# Pulse_Generator.net
KiCad netlist of a schematic drawn in EAGLE
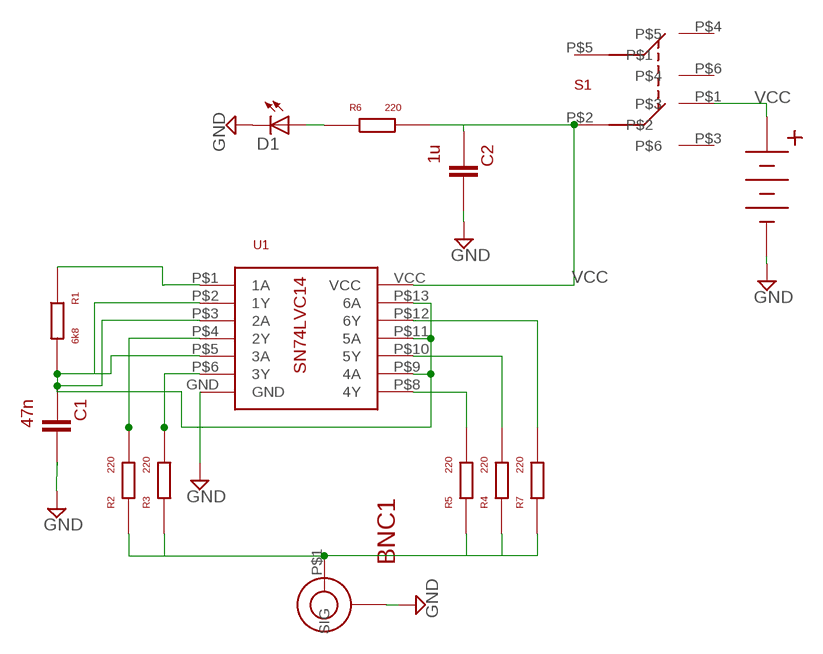
[diagram p0: schematic, sheet 1]

(export (version "E")
  (design (tool "Eeschema 10.0.6"))
  (components
    (comp (ref "BNC1")
      (value "TE-1-337543")
      (footprint "eagle-import:PCBBNC")
      (libsource (lib "eagle-import") (part "TE-1-337543"))
    )
    (comp (ref "C1")
      (value "47n")
      (footprint "eagle-import:1206CAP")
      (libsource (lib "eagle-import") (part "1206LED"))
    )
    (comp (ref "C2")
      (value "1u")
      (footprint "eagle-import:1206CAP")
      (libsource (lib "eagle-import") (part "1206LED"))
    )
    (comp (ref "D1")
      (value "1206LEDDIODE")
      (footprint "eagle-import:1206")
      (libsource (lib "eagle-import") (part "1206LEDDIODE"))
    )
    (comp (ref "R1")
      (value "6k8")
      (footprint "eagle-import:1206")
      (libsource (lib "eagle-import") (part "1206RESISTOR"))
    )
    (comp (ref "R2")
      (value "220")
      (footprint "eagle-import:1206")
      (libsource (lib "eagle-import") (part "1206RESISTOR"))
    )
    (comp (ref "R3")
      (value "220")
      (footprint "eagle-import:1206")
      (libsource (lib "eagle-import") (part "1206RESISTOR"))
    )
    (comp (ref "R4")
      (value "220")
      (footprint "eagle-import:1206")
      (libsource (lib "eagle-import") (part "1206RESISTOR"))
    )
    (comp (ref "R5")
      (value "220")
      (footprint "eagle-import:1206")
      (libsource (lib "eagle-import") (part "1206RESISTOR"))
    )
    (comp (ref "R6")
      (value "220")
      (footprint "eagle-import:1206")
      (libsource (lib "eagle-import") (part "1206RESISTOR"))
    )
    (comp (ref "R7")
      (value "220")
      (footprint "eagle-import:1206")
      (libsource (lib "eagle-import") (part "1206RESISTOR"))
    )
    (comp (ref "S1")
      (value "JS202011SCQN")
      (footprint "eagle-import:JS202011SCQN")
      (libsource (lib "eagle-import") (part "JS202011SCQN"))
    )
    (comp (ref "U$1")
      (value "1042-18650BATTERYHOLE")
      (footprint "eagle-import:BATTHRHOLE")
      (libsource (lib "eagle-import") (part "1042-18650BATTERYHOLE"))
    )
    (comp (ref "U1")
      (value "SN74LVC14A")
      (footprint "eagle-import:SOIC-14")
      (libsource (lib "eagle-import") (part "SN74LVC14A"))
    )
  )
  (nets
    (net (code "1") (name "/VCC") (class "Default")
      (node (ref "C2") (pin "P$2") (pinfunction "P$2_P$2") (pintype "bidirectional"))
      (node (ref "R6") (pin "P$1") (pinfunction "P$1_P$1") (pintype "bidirectional"))
      (node (ref "S1") (pin "P$1") (pinfunction "P$3_P$1") (pintype "bidirectional"))
      (node (ref "S1") (pin "P$2") (pinfunction "P$2_P$2") (pintype "bidirectional"))
      (node (ref "U$1") (pin "VCC") (pinfunction "VCC_VCC") (pintype "power_in"))
      (node (ref "U1") (pin "VCC") (pinfunction "VCC_VCC") (pintype "power_in"))
    )
    (net (code "2") (name "GND") (class "Default")
      (node (ref "BNC1") (pin "P$2") (pinfunction "GND_P$2") (pintype "power_in"))
      (node (ref "C1") (pin "P$1") (pinfunction "P$1_P$1") (pintype "bidirectional"))
      (node (ref "C2") (pin "P$1") (pinfunction "P$1_P$1") (pintype "bidirectional"))
      (node (ref "D1") (pin "P$2") (pinfunction "C_P$2") (pintype "passive"))
      (node (ref "U$1") (pin "GND") (pinfunction "GND_GND") (pintype "power_in"))
      (node (ref "U1") (pin "GND") (pinfunction "GND_GND") (pintype "power_in"))
    )
    (net (code "3") (name "Net-(BNC1-SIG)") (class "Default")
      (node (ref "BNC1") (pin "P$1") (pinfunction "SIG_P$1") (pintype "bidirectional"))
      (node (ref "R2") (pin "P$2") (pinfunction "P$2_P$2") (pintype "bidirectional"))
      (node (ref "R3") (pin "P$2") (pinfunction "P$2_P$2") (pintype "bidirectional"))
      (node (ref "R4") (pin "P$2") (pinfunction "P$2_P$2") (pintype "bidirectional"))
      (node (ref "R5") (pin "P$2") (pinfunction "P$2_P$2") (pintype "bidirectional"))
      (node (ref "R7") (pin "P$2") (pinfunction "P$2_P$2") (pintype "bidirectional"))
    )
    (net (code "4") (name "Net-(D1-A)") (class "Default")
      (node (ref "D1") (pin "P$1") (pinfunction "A_P$1") (pintype "passive"))
      (node (ref "R6") (pin "P$2") (pinfunction "P$2_P$2") (pintype "bidirectional"))
    )
    (net (code "5") (name "Net-(U1-1A)") (class "Default")
      (node (ref "R1") (pin "P$2") (pinfunction "P$2_P$2") (pintype "bidirectional"))
      (node (ref "U1") (pin "P$1") (pinfunction "1A_P$1") (pintype "input"))
    )
    (net (code "6") (name "Net-(U1-1Y)") (class "Default")
      (node (ref "C1") (pin "P$2") (pinfunction "P$2_P$2") (pintype "bidirectional"))
      (node (ref "R1") (pin "P$1") (pinfunction "P$1_P$1") (pintype "bidirectional"))
      (node (ref "U1") (pin "P$11") (pinfunction "5A_P$11") (pintype "input"))
      (node (ref "U1") (pin "P$13") (pinfunction "6A_P$13") (pintype "input"))
      (node (ref "U1") (pin "P$2") (pinfunction "1Y_P$2") (pintype "output"))
      (node (ref "U1") (pin "P$3") (pinfunction "2A_P$3") (pintype "input"))
      (node (ref "U1") (pin "P$5") (pinfunction "3A_P$5") (pintype "input"))
      (node (ref "U1") (pin "P$9") (pinfunction "4A_P$9") (pintype "input"))
    )
    (net (code "7") (name "Net-(U1-2Y)") (class "Default")
      (node (ref "R2") (pin "P$1") (pinfunction "P$1_P$1") (pintype "bidirectional"))
      (node (ref "U1") (pin "P$4") (pinfunction "2Y_P$4") (pintype "output"))
    )
    (net (code "8") (name "Net-(U1-3Y)") (class "Default")
      (node (ref "R3") (pin "P$1") (pinfunction "P$1_P$1") (pintype "bidirectional"))
      (node (ref "U1") (pin "P$6") (pinfunction "3Y_P$6") (pintype "output"))
    )
    (net (code "9") (name "Net-(U1-4Y)") (class "Default")
      (node (ref "R5") (pin "P$1") (pinfunction "P$1_P$1") (pintype "bidirectional"))
      (node (ref "U1") (pin "P$8") (pinfunction "4Y_P$8") (pintype "output"))
    )
    (net (code "10") (name "Net-(U1-5Y)") (class "Default")
      (node (ref "R4") (pin "P$1") (pinfunction "P$1_P$1") (pintype "bidirectional"))
      (node (ref "U1") (pin "P$10") (pinfunction "5Y_P$10") (pintype "output"))
    )
    (net (code "11") (name "Net-(U1-6Y)") (class "Default")
      (node (ref "R7") (pin "P$1") (pinfunction "P$1_P$1") (pintype "bidirectional"))
      (node (ref "U1") (pin "P$12") (pinfunction "6Y_P$12") (pintype "output"))
    )
    (net (code "12") (name "unconnected-(S1-P$1-PadP$5)") (class "Default")
      (node (ref "S1") (pin "P$5") (pinfunction "P$1_P$5") (pintype "bidirectional"))
    )
    (net (code "13") (name "unconnected-(S1-P$4-PadP$6)") (class "Default")
      (node (ref "S1") (pin "P$6") (pinfunction "P$4_P$6") (pintype "bidirectional"))
    )
    (net (code "14") (name "unconnected-(S1-P$5-PadP$4)") (class "Default")
      (node (ref "S1") (pin "P$4") (pinfunction "P$5_P$4") (pintype "bidirectional"))
    )
    (net (code "15") (name "unconnected-(S1-P$6-PadP$3)") (class "Default")
      (node (ref "S1") (pin "P$3") (pinfunction "P$6_P$3") (pintype "bidirectional"))
    )
  )
)
